# led.net
KiCad netlist of a schematic drawn in Altium Designer
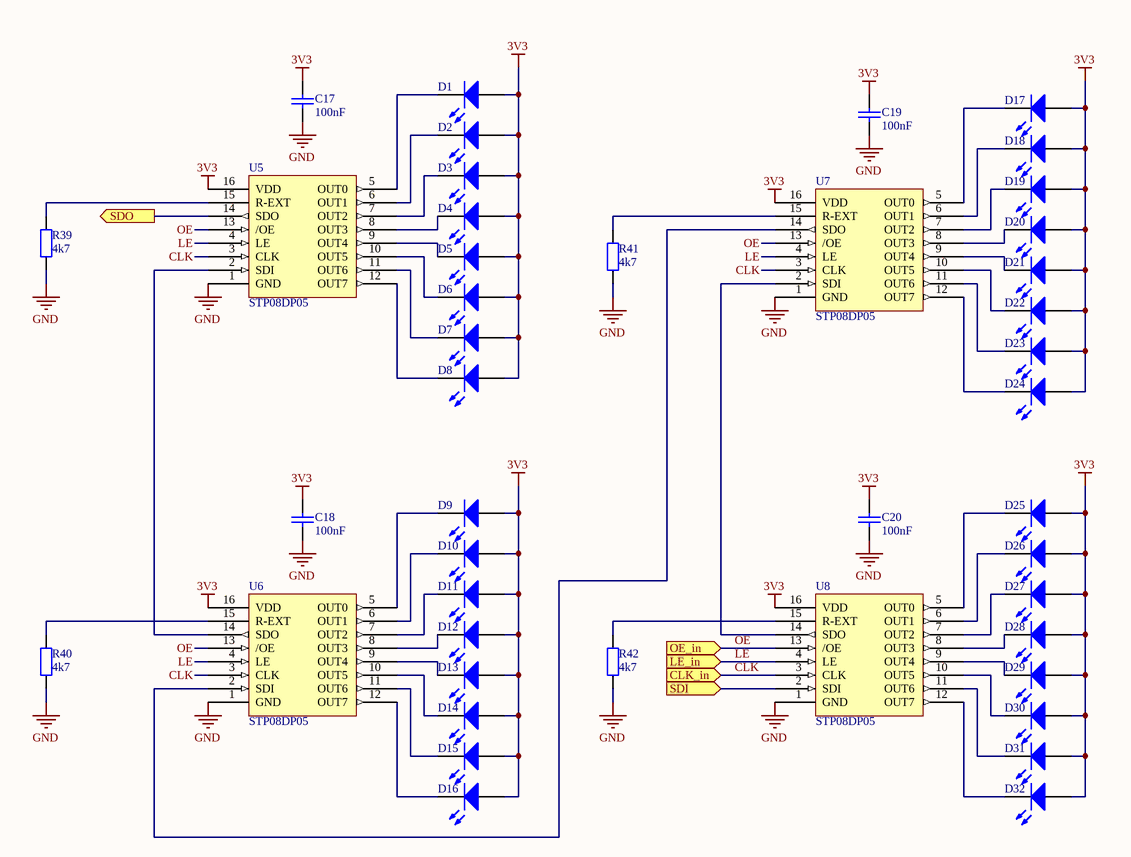
[diagram p0: led.SchDoc]

(export (version "E")
  (design (tool "Eeschema 10.0.6"))
  (components
    (comp (ref "C17")
      (value "100nF")
      (footprint "FP_0805_CAP_085")
      (description "Capacitor")
      (libsource (lib "hallglib") (part "CAP"))
    )
    (comp (ref "C18")
      (value "100nF")
      (footprint "FP_0805_CAP_085")
      (description "Capacitor")
      (libsource (lib "hallglib") (part "CAP"))
    )
    (comp (ref "C19")
      (value "100nF")
      (footprint "FP_0805_CAP_085")
      (description "Capacitor")
      (libsource (lib "hallglib") (part "CAP"))
    )
    (comp (ref "C20")
      (value "100nF")
      (footprint "FP_0805_CAP_085")
      (description "Capacitor")
      (libsource (lib "hallglib") (part "CAP"))
    )
    (comp (ref "D1")
      (value "LED")
      (footprint "FP_0805_LED_RED")
      (description "Typical RED GaAs LED")
      (libsource (lib "hallglib") (part "LED"))
    )
    (comp (ref "D2")
      (value "LED")
      (footprint "FP_0805_LED_RED")
      (description "Typical RED GaAs LED")
      (libsource (lib "hallglib") (part "LED"))
    )
    (comp (ref "D3")
      (value "LED")
      (footprint "FP_0805_LED_RED")
      (description "Typical RED GaAs LED")
      (libsource (lib "hallglib") (part "LED"))
    )
    (comp (ref "D4")
      (value "LED")
      (footprint "FP_0805_LED_RED")
      (description "Typical RED GaAs LED")
      (libsource (lib "hallglib") (part "LED"))
    )
    (comp (ref "D5")
      (value "LED")
      (footprint "FP_0805_LED_RED")
      (description "Typical RED GaAs LED")
      (libsource (lib "hallglib") (part "LED"))
    )
    (comp (ref "D6")
      (value "LED")
      (footprint "FP_0805_LED_RED")
      (description "Typical RED GaAs LED")
      (libsource (lib "hallglib") (part "LED"))
    )
    (comp (ref "D7")
      (value "LED")
      (footprint "FP_0805_LED_RED")
      (description "Typical RED GaAs LED")
      (libsource (lib "hallglib") (part "LED"))
    )
    (comp (ref "D8")
      (value "LED")
      (footprint "FP_0805_LED_RED")
      (description "Typical RED GaAs LED")
      (libsource (lib "hallglib") (part "LED"))
    )
    (comp (ref "D9")
      (value "LED")
      (footprint "FP_0805_LED_RED")
      (description "Typical RED GaAs LED")
      (libsource (lib "hallglib") (part "LED"))
    )
    (comp (ref "D10")
      (value "LED")
      (footprint "FP_0805_LED_RED")
      (description "Typical RED GaAs LED")
      (libsource (lib "hallglib") (part "LED"))
    )
    (comp (ref "D11")
      (value "LED")
      (footprint "FP_0805_LED_RED")
      (description "Typical RED GaAs LED")
      (libsource (lib "hallglib") (part "LED"))
    )
    (comp (ref "D12")
      (value "LED")
      (footprint "FP_0805_LED_RED")
      (description "Typical RED GaAs LED")
      (libsource (lib "hallglib") (part "LED"))
    )
    (comp (ref "D13")
      (value "LED")
      (footprint "FP_0805_LED_RED")
      (description "Typical RED GaAs LED")
      (libsource (lib "hallglib") (part "LED"))
    )
    (comp (ref "D14")
      (value "LED")
      (footprint "FP_0805_LED_RED")
      (description "Typical RED GaAs LED")
      (libsource (lib "hallglib") (part "LED"))
    )
    (comp (ref "D15")
      (value "LED")
      (footprint "FP_0805_LED_RED")
      (description "Typical RED GaAs LED")
      (libsource (lib "hallglib") (part "LED"))
    )
    (comp (ref "D16")
      (value "LED")
      (footprint "FP_0805_LED_RED")
      (description "Typical RED GaAs LED")
      (libsource (lib "hallglib") (part "LED"))
    )
    (comp (ref "D17")
      (value "LED")
      (footprint "FP_0805_LED_RED")
      (description "Typical RED GaAs LED")
      (libsource (lib "hallglib") (part "LED"))
    )
    (comp (ref "D18")
      (value "LED")
      (footprint "FP_0805_LED_RED")
      (description "Typical RED GaAs LED")
      (libsource (lib "hallglib") (part "LED"))
    )
    (comp (ref "D19")
      (value "LED")
      (footprint "FP_0805_LED_RED")
      (description "Typical RED GaAs LED")
      (libsource (lib "hallglib") (part "LED"))
    )
    (comp (ref "D20")
      (value "LED")
      (footprint "FP_0805_LED_RED")
      (description "Typical RED GaAs LED")
      (libsource (lib "hallglib") (part "LED"))
    )
    (comp (ref "D21")
      (value "LED")
      (footprint "FP_0805_LED_RED")
      (description "Typical RED GaAs LED")
      (libsource (lib "hallglib") (part "LED"))
    )
    (comp (ref "D22")
      (value "LED")
      (footprint "FP_0805_LED_RED")
      (description "Typical RED GaAs LED")
      (libsource (lib "hallglib") (part "LED"))
    )
    (comp (ref "D23")
      (value "LED")
      (footprint "FP_0805_LED_RED")
      (description "Typical RED GaAs LED")
      (libsource (lib "hallglib") (part "LED"))
    )
    (comp (ref "D24")
      (value "LED")
      (footprint "FP_0805_LED_RED")
      (description "Typical RED GaAs LED")
      (libsource (lib "hallglib") (part "LED"))
    )
    (comp (ref "D25")
      (value "LED")
      (footprint "FP_0805_LED_RED")
      (description "Typical RED GaAs LED")
      (libsource (lib "hallglib") (part "LED"))
    )
    (comp (ref "D26")
      (value "LED")
      (footprint "FP_0805_LED_RED")
      (description "Typical RED GaAs LED")
      (libsource (lib "hallglib") (part "LED"))
    )
    (comp (ref "D27")
      (value "LED")
      (footprint "FP_0805_LED_RED")
      (description "Typical RED GaAs LED")
      (libsource (lib "hallglib") (part "LED"))
    )
    (comp (ref "D28")
      (value "LED")
      (footprint "FP_0805_LED_RED")
      (description "Typical RED GaAs LED")
      (libsource (lib "hallglib") (part "LED"))
    )
    (comp (ref "D29")
      (value "LED")
      (footprint "FP_0805_LED_RED")
      (description "Typical RED GaAs LED")
      (libsource (lib "hallglib") (part "LED"))
    )
    (comp (ref "D30")
      (value "LED")
      (footprint "FP_0805_LED_RED")
      (description "Typical RED GaAs LED")
      (libsource (lib "hallglib") (part "LED"))
    )
    (comp (ref "D31")
      (value "LED")
      (footprint "FP_0805_LED_RED")
      (description "Typical RED GaAs LED")
      (libsource (lib "hallglib") (part "LED"))
    )
    (comp (ref "D32")
      (value "LED")
      (footprint "FP_0805_LED_RED")
      (description "Typical RED GaAs LED")
      (libsource (lib "hallglib") (part "LED"))
    )
    (comp (ref "R39")
      (value "4k7")
      (footprint "FP_0805_RES")
      (description "Resistor")
      (libsource (lib "hallglib") (part "RES"))
    )
    (comp (ref "R40")
      (value "4k7")
      (footprint "FP_0805_RES")
      (description "Resistor")
      (libsource (lib "hallglib") (part "RES"))
    )
    (comp (ref "R41")
      (value "4k7")
      (footprint "FP_0805_RES")
      (description "Resistor")
      (libsource (lib "hallglib") (part "RES"))
    )
    (comp (ref "R42")
      (value "4k7")
      (footprint "FP_0805_RES")
      (description "Resistor")
      (libsource (lib "hallglib") (part "RES"))
    )
    (comp (ref "U5")
      (value "STP08DP05")
      (footprint "TSSOP16_2")
      (description "LED driver [8]")
      (libsource (lib "line-sensor") (part "STP08DP05"))
    )
    (comp (ref "U6")
      (value "STP08DP05")
      (footprint "TSSOP16_2")
      (description "LED driver [8]")
      (libsource (lib "line-sensor") (part "STP08DP05"))
    )
    (comp (ref "U7")
      (value "STP08DP05")
      (footprint "TSSOP16_2")
      (description "LED driver [8]")
      (libsource (lib "line-sensor") (part "STP08DP05"))
    )
    (comp (ref "U8")
      (value "STP08DP05")
      (footprint "TSSOP16_2")
      (description "LED driver [8]")
      (libsource (lib "line-sensor") (part "STP08DP05"))
    )
  )
  (nets
    (net (code "1") (name "/CLK") (class "Default")
      (node (ref "U5") (pin "3") (pinfunction "CLK_3") (pintype "input"))
      (node (ref "U6") (pin "3") (pinfunction "CLK_3") (pintype "input"))
      (node (ref "U7") (pin "3") (pinfunction "CLK_3") (pintype "input"))
      (node (ref "U8") (pin "3") (pinfunction "CLK_3") (pintype "input"))
    )
    (net (code "2") (name "/LE") (class "Default")
      (node (ref "U5") (pin "4") (pinfunction "LE_4") (pintype "input"))
      (node (ref "U6") (pin "4") (pinfunction "LE_4") (pintype "input"))
      (node (ref "U7") (pin "4") (pinfunction "LE_4") (pintype "input"))
      (node (ref "U8") (pin "4") (pinfunction "LE_4") (pintype "input"))
    )
    (net (code "3") (name "/OE") (class "Default")
      (node (ref "U5") (pin "13") (pinfunction "/OE_13") (pintype "input"))
      (node (ref "U6") (pin "13") (pinfunction "/OE_13") (pintype "input"))
      (node (ref "U7") (pin "13") (pinfunction "/OE_13") (pintype "input"))
      (node (ref "U8") (pin "13") (pinfunction "/OE_13") (pintype "input"))
    )
    (net (code "4") (name "/SDI") (class "Default")
      (node (ref "U8") (pin "2") (pinfunction "SDI_2") (pintype "input"))
    )
    (net (code "5") (name "/SDO") (class "Default")
      (node (ref "U5") (pin "14") (pinfunction "SDO_14") (pintype "output"))
    )
    (net (code "6") (name "3V3") (class "Default")
      (node (ref "C17") (pin "2") (pinfunction "2_2") (pintype "passive"))
      (node (ref "C18") (pin "2") (pinfunction "2_2") (pintype "passive"))
      (node (ref "C19") (pin "2") (pinfunction "2_2") (pintype "passive"))
      (node (ref "C20") (pin "2") (pinfunction "2_2") (pintype "passive"))
      (node (ref "D1") (pin "1") (pinfunction "A_1") (pintype "passive"))
      (node (ref "D10") (pin "1") (pinfunction "A_1") (pintype "passive"))
      (node (ref "D11") (pin "1") (pinfunction "A_1") (pintype "passive"))
      (node (ref "D12") (pin "1") (pinfunction "A_1") (pintype "passive"))
      (node (ref "D13") (pin "1") (pinfunction "A_1") (pintype "passive"))
      (node (ref "D14") (pin "1") (pinfunction "A_1") (pintype "passive"))
      (node (ref "D15") (pin "1") (pinfunction "A_1") (pintype "passive"))
      (node (ref "D16") (pin "1") (pinfunction "A_1") (pintype "passive"))
      (node (ref "D17") (pin "1") (pinfunction "A_1") (pintype "passive"))
      (node (ref "D18") (pin "1") (pinfunction "A_1") (pintype "passive"))
      (node (ref "D19") (pin "1") (pinfunction "A_1") (pintype "passive"))
      (node (ref "D2") (pin "1") (pinfunction "A_1") (pintype "passive"))
      (node (ref "D20") (pin "1") (pinfunction "A_1") (pintype "passive"))
      (node (ref "D21") (pin "1") (pinfunction "A_1") (pintype "passive"))
      (node (ref "D22") (pin "1") (pinfunction "A_1") (pintype "passive"))
      (node (ref "D23") (pin "1") (pinfunction "A_1") (pintype "passive"))
      (node (ref "D24") (pin "1") (pinfunction "A_1") (pintype "passive"))
      (node (ref "D25") (pin "1") (pinfunction "A_1") (pintype "passive"))
      (node (ref "D26") (pin "1") (pinfunction "A_1") (pintype "passive"))
      (node (ref "D27") (pin "1") (pinfunction "A_1") (pintype "passive"))
      (node (ref "D28") (pin "1") (pinfunction "A_1") (pintype "passive"))
      (node (ref "D29") (pin "1") (pinfunction "A_1") (pintype "passive"))
      (node (ref "D3") (pin "1") (pinfunction "A_1") (pintype "passive"))
      (node (ref "D30") (pin "1") (pinfunction "A_1") (pintype "passive"))
      (node (ref "D31") (pin "1") (pinfunction "A_1") (pintype "passive"))
      (node (ref "D32") (pin "1") (pinfunction "A_1") (pintype "passive"))
      (node (ref "D4") (pin "1") (pinfunction "A_1") (pintype "passive"))
      (node (ref "D5") (pin "1") (pinfunction "A_1") (pintype "passive"))
      (node (ref "D6") (pin "1") (pinfunction "A_1") (pintype "passive"))
      (node (ref "D7") (pin "1") (pinfunction "A_1") (pintype "passive"))
      (node (ref "D8") (pin "1") (pinfunction "A_1") (pintype "passive"))
      (node (ref "D9") (pin "1") (pinfunction "A_1") (pintype "passive"))
      (node (ref "U5") (pin "16") (pinfunction "VDD_16") (pintype "passive"))
      (node (ref "U6") (pin "16") (pinfunction "VDD_16") (pintype "passive"))
      (node (ref "U7") (pin "16") (pinfunction "VDD_16") (pintype "passive"))
      (node (ref "U8") (pin "16") (pinfunction "VDD_16") (pintype "passive"))
    )
    (net (code "7") (name "GND") (class "Default")
      (node (ref "C17") (pin "1") (pinfunction "1_1") (pintype "passive"))
      (node (ref "C18") (pin "1") (pinfunction "1_1") (pintype "passive"))
      (node (ref "C19") (pin "1") (pinfunction "1_1") (pintype "passive"))
      (node (ref "C20") (pin "1") (pinfunction "1_1") (pintype "passive"))
      (node (ref "R39") (pin "2") (pinfunction "2_2") (pintype "passive"))
      (node (ref "R40") (pin "2") (pinfunction "2_2") (pintype "passive"))
      (node (ref "R41") (pin "2") (pinfunction "2_2") (pintype "passive"))
      (node (ref "R42") (pin "2") (pinfunction "2_2") (pintype "passive"))
      (node (ref "U5") (pin "1") (pinfunction "GND_1") (pintype "power_in"))
      (node (ref "U6") (pin "1") (pinfunction "GND_1") (pintype "power_in"))
      (node (ref "U7") (pin "1") (pinfunction "GND_1") (pintype "power_in"))
      (node (ref "U8") (pin "1") (pinfunction "GND_1") (pintype "power_in"))
    )
    (net (code "8") (name "Net-(D1-K)") (class "Default")
      (node (ref "D1") (pin "2") (pinfunction "K_2") (pintype "passive"))
      (node (ref "U5") (pin "5") (pinfunction "OUT0_5") (pintype "output"))
    )
    (net (code "9") (name "Net-(D2-K)") (class "Default")
      (node (ref "D2") (pin "2") (pinfunction "K_2") (pintype "passive"))
      (node (ref "U5") (pin "6") (pinfunction "OUT1_6") (pintype "output"))
    )
    (net (code "10") (name "Net-(D3-K)") (class "Default")
      (node (ref "D3") (pin "2") (pinfunction "K_2") (pintype "passive"))
      (node (ref "U5") (pin "7") (pinfunction "OUT2_7") (pintype "output"))
    )
    (net (code "11") (name "Net-(D4-K)") (class "Default")
      (node (ref "D4") (pin "2") (pinfunction "K_2") (pintype "passive"))
      (node (ref "U5") (pin "8") (pinfunction "OUT3_8") (pintype "output"))
    )
    (net (code "12") (name "Net-(D5-K)") (class "Default")
      (node (ref "D5") (pin "2") (pinfunction "K_2") (pintype "passive"))
      (node (ref "U5") (pin "9") (pinfunction "OUT4_9") (pintype "output"))
    )
    (net (code "13") (name "Net-(D6-K)") (class "Default")
      (node (ref "D6") (pin "2") (pinfunction "K_2") (pintype "passive"))
      (node (ref "U5") (pin "10") (pinfunction "OUT5_10") (pintype "output"))
    )
    (net (code "14") (name "Net-(D7-K)") (class "Default")
      (node (ref "D7") (pin "2") (pinfunction "K_2") (pintype "passive"))
      (node (ref "U5") (pin "11") (pinfunction "OUT6_11") (pintype "output"))
    )
    (net (code "15") (name "Net-(D8-K)") (class "Default")
      (node (ref "D8") (pin "2") (pinfunction "K_2") (pintype "passive"))
      (node (ref "U5") (pin "12") (pinfunction "OUT7_12") (pintype "output"))
    )
    (net (code "16") (name "Net-(D9-K)") (class "Default")
      (node (ref "D9") (pin "2") (pinfunction "K_2") (pintype "passive"))
      (node (ref "U6") (pin "5") (pinfunction "OUT0_5") (pintype "output"))
    )
    (net (code "17") (name "Net-(D10-K)") (class "Default")
      (node (ref "D10") (pin "2") (pinfunction "K_2") (pintype "passive"))
      (node (ref "U6") (pin "6") (pinfunction "OUT1_6") (pintype "output"))
    )
    (net (code "18") (name "Net-(D11-K)") (class "Default")
      (node (ref "D11") (pin "2") (pinfunction "K_2") (pintype "passive"))
      (node (ref "U6") (pin "7") (pinfunction "OUT2_7") (pintype "output"))
    )
    (net (code "19") (name "Net-(D12-K)") (class "Default")
      (node (ref "D12") (pin "2") (pinfunction "K_2") (pintype "passive"))
      (node (ref "U6") (pin "8") (pinfunction "OUT3_8") (pintype "output"))
    )
    (net (code "20") (name "Net-(D13-K)") (class "Default")
      (node (ref "D13") (pin "2") (pinfunction "K_2") (pintype "passive"))
      (node (ref "U6") (pin "9") (pinfunction "OUT4_9") (pintype "output"))
    )
    (net (code "21") (name "Net-(D14-K)") (class "Default")
      (node (ref "D14") (pin "2") (pinfunction "K_2") (pintype "passive"))
      (node (ref "U6") (pin "10") (pinfunction "OUT5_10") (pintype "output"))
    )
    (net (code "22") (name "Net-(D15-K)") (class "Default")
      (node (ref "D15") (pin "2") (pinfunction "K_2") (pintype "passive"))
      (node (ref "U6") (pin "11") (pinfunction "OUT6_11") (pintype "output"))
    )
    (net (code "23") (name "Net-(D16-K)") (class "Default")
      (node (ref "D16") (pin "2") (pinfunction "K_2") (pintype "passive"))
      (node (ref "U6") (pin "12") (pinfunction "OUT7_12") (pintype "output"))
    )
    (net (code "24") (name "Net-(D17-K)") (class "Default")
      (node (ref "D17") (pin "2") (pinfunction "K_2") (pintype "passive"))
      (node (ref "U7") (pin "5") (pinfunction "OUT0_5") (pintype "output"))
    )
    (net (code "25") (name "Net-(D18-K)") (class "Default")
      (node (ref "D18") (pin "2") (pinfunction "K_2") (pintype "passive"))
      (node (ref "U7") (pin "6") (pinfunction "OUT1_6") (pintype "output"))
    )
    (net (code "26") (name "Net-(D19-K)") (class "Default")
      (node (ref "D19") (pin "2") (pinfunction "K_2") (pintype "passive"))
      (node (ref "U7") (pin "7") (pinfunction "OUT2_7") (pintype "output"))
    )
    (net (code "27") (name "Net-(D20-K)") (class "Default")
      (node (ref "D20") (pin "2") (pinfunction "K_2") (pintype "passive"))
      (node (ref "U7") (pin "8") (pinfunction "OUT3_8") (pintype "output"))
    )
    (net (code "28") (name "Net-(D21-K)") (class "Default")
      (node (ref "D21") (pin "2") (pinfunction "K_2") (pintype "passive"))
      (node (ref "U7") (pin "9") (pinfunction "OUT4_9") (pintype "output"))
    )
    (net (code "29") (name "Net-(D22-K)") (class "Default")
      (node (ref "D22") (pin "2") (pinfunction "K_2") (pintype "passive"))
      (node (ref "U7") (pin "10") (pinfunction "OUT5_10") (pintype "output"))
    )
    (net (code "30") (name "Net-(D23-K)") (class "Default")
      (node (ref "D23") (pin "2") (pinfunction "K_2") (pintype "passive"))
      (node (ref "U7") (pin "11") (pinfunction "OUT6_11") (pintype "output"))
    )
    (net (code "31") (name "Net-(D24-K)") (class "Default")
      (node (ref "D24") (pin "2") (pinfunction "K_2") (pintype "passive"))
      (node (ref "U7") (pin "12") (pinfunction "OUT7_12") (pintype "output"))
    )
    (net (code "32") (name "Net-(D25-K)") (class "Default")
      (node (ref "D25") (pin "2") (pinfunction "K_2") (pintype "passive"))
      (node (ref "U8") (pin "5") (pinfunction "OUT0_5") (pintype "output"))
    )
    (net (code "33") (name "Net-(D26-K)") (class "Default")
      (node (ref "D26") (pin "2") (pinfunction "K_2") (pintype "passive"))
      (node (ref "U8") (pin "6") (pinfunction "OUT1_6") (pintype "output"))
    )
    (net (code "34") (name "Net-(D27-K)") (class "Default")
      (node (ref "D27") (pin "2") (pinfunction "K_2") (pintype "passive"))
      (node (ref "U8") (pin "7") (pinfunction "OUT2_7") (pintype "output"))
    )
    (net (code "35") (name "Net-(D28-K)") (class "Default")
      (node (ref "D28") (pin "2") (pinfunction "K_2") (pintype "passive"))
      (node (ref "U8") (pin "8") (pinfunction "OUT3_8") (pintype "output"))
    )
    (net (code "36") (name "Net-(D29-K)") (class "Default")
      (node (ref "D29") (pin "2") (pinfunction "K_2") (pintype "passive"))
      (node (ref "U8") (pin "9") (pinfunction "OUT4_9") (pintype "output"))
    )
    (net (code "37") (name "Net-(D30-K)") (class "Default")
      (node (ref "D30") (pin "2") (pinfunction "K_2") (pintype "passive"))
      (node (ref "U8") (pin "10") (pinfunction "OUT5_10") (pintype "output"))
    )
    (net (code "38") (name "Net-(D31-K)") (class "Default")
      (node (ref "D31") (pin "2") (pinfunction "K_2") (pintype "passive"))
      (node (ref "U8") (pin "11") (pinfunction "OUT6_11") (pintype "output"))
    )
    (net (code "39") (name "Net-(D32-K)") (class "Default")
      (node (ref "D32") (pin "2") (pinfunction "K_2") (pintype "passive"))
      (node (ref "U8") (pin "12") (pinfunction "OUT7_12") (pintype "output"))
    )
    (net (code "40") (name "Net-(U5-R-EXT)") (class "Default")
      (node (ref "R39") (pin "1") (pinfunction "1_1") (pintype "passive"))
      (node (ref "U5") (pin "15") (pinfunction "R-EXT_15") (pintype "passive"))
    )
    (net (code "41") (name "Net-(U5-SDI)") (class "Default")
      (node (ref "U5") (pin "2") (pinfunction "SDI_2") (pintype "input"))
      (node (ref "U6") (pin "14") (pinfunction "SDO_14") (pintype "output"))
    )
    (net (code "42") (name "Net-(U6-R-EXT)") (class "Default")
      (node (ref "R40") (pin "1") (pinfunction "1_1") (pintype "passive"))
      (node (ref "U6") (pin "15") (pinfunction "R-EXT_15") (pintype "passive"))
    )
    (net (code "43") (name "Net-(U6-SDI)") (class "Default")
      (node (ref "U6") (pin "2") (pinfunction "SDI_2") (pintype "input"))
      (node (ref "U7") (pin "14") (pinfunction "SDO_14") (pintype "output"))
    )
    (net (code "44") (name "Net-(U7-R-EXT)") (class "Default")
      (node (ref "R41") (pin "1") (pinfunction "1_1") (pintype "passive"))
      (node (ref "U7") (pin "15") (pinfunction "R-EXT_15") (pintype "passive"))
    )
    (net (code "45") (name "Net-(U7-SDI)") (class "Default")
      (node (ref "U7") (pin "2") (pinfunction "SDI_2") (pintype "input"))
      (node (ref "U8") (pin "14") (pinfunction "SDO_14") (pintype "output"))
    )
    (net (code "46") (name "Net-(U8-R-EXT)") (class "Default")
      (node (ref "R42") (pin "1") (pinfunction "1_1") (pintype "passive"))
      (node (ref "U8") (pin "15") (pinfunction "R-EXT_15") (pintype "passive"))
    )
  )
)
